# E180-Z8910SX.net
KiCad netlist of a schematic drawn in EAGLE
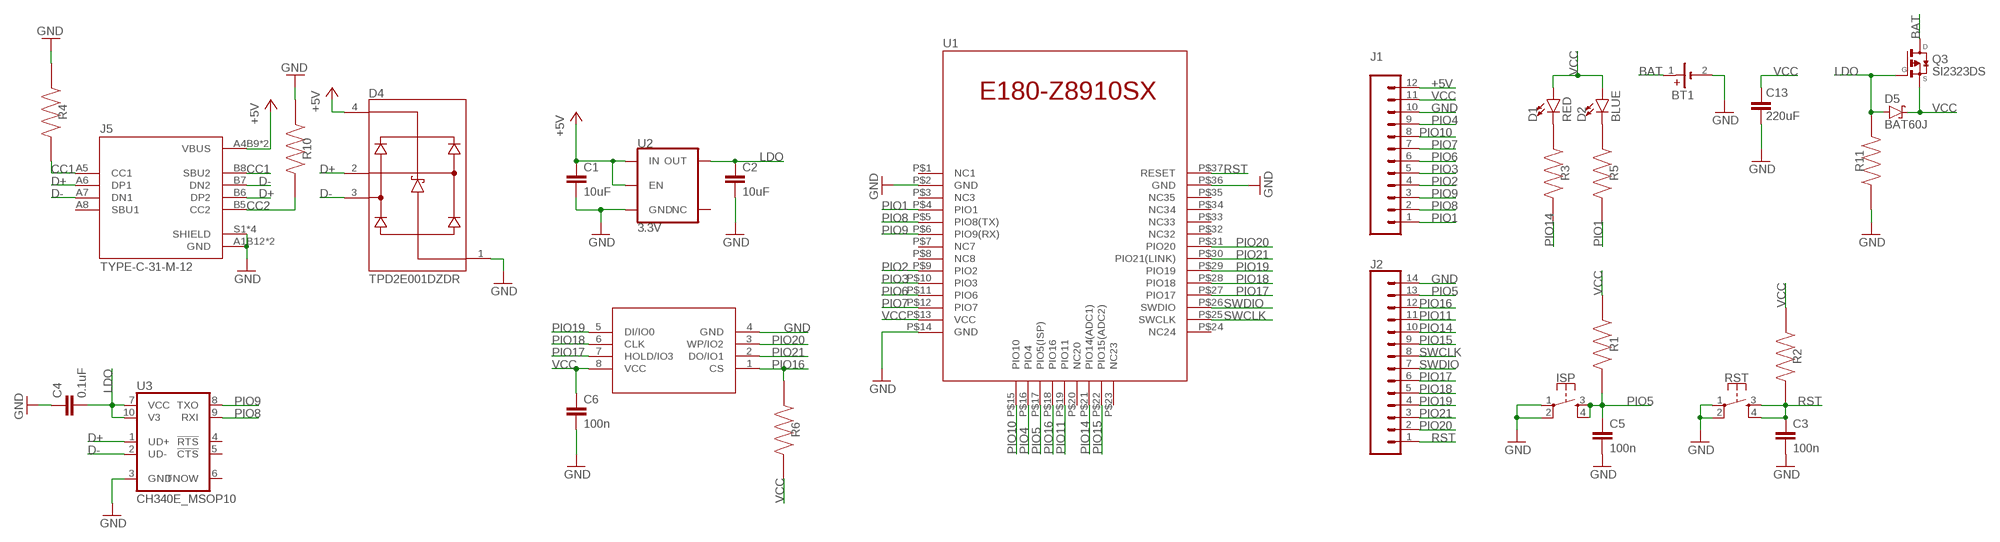
[diagram p0: schematic, sheet 1]

(export (version "E")
  (design (tool "Eeschema 10.0.6"))
  (components
    (comp (ref "BT1")
      (value "79527141")
      (footprint "eagle-import:79527141")
      (fields
        (field (name "DIGIKEY_PART_NO") "732-12325-2-ND")
        (field (name "MANUFACTURER") "Wurth Electronics Inc.")
        (field (name "CREATED_BY") "PCBLayout.com")
      )
      (libsource (lib "eagle-import") (part "79527141"))
    )
    (comp (ref "C1")
      (value "10uF")
      (footprint "eagle-import:0603")
      (libsource (lib "eagle-import") (part "10UF-0603-6.3V-20%"))
    )
    (comp (ref "C2")
      (value "10uF")
      (footprint "eagle-import:0603")
      (libsource (lib "eagle-import") (part "10UF-0603-6.3V-20%"))
    )
    (comp (ref "C3")
      (value "100n")
      (footprint "eagle-import:0603")
      (libsource (lib "eagle-import") (part "SparkFun-Capacitors_510_0.1UF-0603-25V-5%"))
    )
    (comp (ref "C4")
      (value "0.1uF")
      (footprint "eagle-import:0603")
      (libsource (lib "eagle-import") (part "0.1UF-0603-25V-(+80/-20%)"))
    )
    (comp (ref "C5")
      (value "100n")
      (footprint "eagle-import:0603")
      (libsource (lib "eagle-import") (part "SparkFun-Capacitors_510_0.1UF-0603-25V-5%"))
    )
    (comp (ref "C6")
      (value "100n")
      (footprint "eagle-import:0603")
      (libsource (lib "eagle-import") (part "SparkFun-Capacitors_510_0.1UF-0603-25V-5%"))
    )
    (comp (ref "C13")
      (value "220uF")
      (footprint "eagle-import:CAPM7343X310")
      (libsource (lib "eagle-import") (part "CTANTALUM-2917(7343-METRIC)_"))
    )
    (comp (ref "D1")
      (value "RED")
      (footprint "eagle-import:LED-0603")
      (libsource (lib "eagle-import") (part "LED-RED0603"))
    )
    (comp (ref "D2")
      (value "BLUE")
      (footprint "eagle-import:LED-0603")
      (libsource (lib "eagle-import") (part "LED-GREEN0603"))
    )
    (comp (ref "D4")
      (value "TPD2E001DZDR")
      (footprint "eagle-import:SOT192P237X122-4N")
      (fields (field (name "MF") "Texas Instruments"))
      (libsource (lib "eagle-import") (part "TPD2E001DZDR"))
    )
    (comp (ref "D5")
      (value "BAT60J")
      (footprint "eagle-import:SOD323_ST")
      (libsource (lib "eagle-import") (part "BAT60J"))
    )
    (comp (ref "ISP")
      (value "MOMENTARY-SWITCH-SPST-2-SMD-4.6X2.8MM")
      (footprint "eagle-import:TACTILE_SWITCH_SMD_4.6X2.8MM")
      (libsource (lib "eagle-import") (part "MOMENTARY-SWITCH-SPST-2-SMD-4.6X2.8MM"))
    )
    (comp (ref "J1")
      (value "CONN_12NO_SILK")
      (footprint "eagle-import:1X12_NO_SILK")
      (libsource (lib "eagle-import") (part "CONN_12NO_SILK"))
    )
    (comp (ref "J2")
      (value "CONN_14NO_SILK")
      (footprint "eagle-import:1X14_NO_SILK")
      (libsource (lib "eagle-import") (part "CONN_14NO_SILK"))
    )
    (comp (ref "J5")
      (value "TYPE-C-31-M-12")
      (footprint "eagle-import:HRO_TYPE-C-31-M-12")
      (fields (field (name "MF") "HRO Electronics Co., Ltd."))
      (libsource (lib "eagle-import") (part "TYPE-C-31-M-12"))
    )
    (comp (ref "Q3")
      (value "SI2323DS")
      (footprint "eagle-import:SOT23")
      (fields (field (name "MF") "Vishay Siliconix"))
      (libsource (lib "eagle-import") (part "SI2323DS"))
    )
    (comp (ref "R1")
      (value "10k")
      (footprint "eagle-import:RESC1005X40N")
      (fields (field (name "MF") "Yageo") (field (name "MP") "RC0402FR-073M6L"))
      (libsource (lib "eagle-import") (part "RC0402FR-073M6L"))
    )
    (comp (ref "R2")
      (value "10k")
      (footprint "eagle-import:RESC1005X40N")
      (fields (field (name "MF") "Yageo") (field (name "MP") "RC0402FR-073M6L"))
      (libsource (lib "eagle-import") (part "RC0402FR-073M6L"))
    )
    (comp (ref "R3")
      (value "2k")
      (footprint "eagle-import:RESC1005X40N")
      (fields (field (name "MF") "Yageo") (field (name "MP") "RC0402FR-073M6L"))
      (libsource (lib "eagle-import") (part "RC0402FR-073M6L"))
    )
    (comp (ref "R4")
      (value "5.1k")
      (footprint "eagle-import:RESC1005X40N")
      (fields (field (name "MF") "Yageo") (field (name "MP") "RC0402FR-073M6L"))
      (libsource (lib "eagle-import") (part "RC0402FR-073M6L"))
    )
    (comp (ref "R5")
      (value "2k")
      (footprint "eagle-import:RESC1005X40N")
      (fields (field (name "MF") "Yageo") (field (name "MP") "RC0402FR-073M6L"))
      (libsource (lib "eagle-import") (part "RC0402FR-073M6L"))
    )
    (comp (ref "R6")
      (value "100k")
      (footprint "eagle-import:RESC1005X40N")
      (fields (field (name "MF") "Yageo") (field (name "MP") "RC0402FR-073M6L"))
      (libsource (lib "eagle-import") (part "RC0402FR-073M6L"))
    )
    (comp (ref "R10")
      (value "5.1k")
      (footprint "eagle-import:RESC1005X40N")
      (fields (field (name "MF") "Yageo") (field (name "MP") "RC0402FR-073M6L"))
      (libsource (lib "eagle-import") (part "RC0402FR-073M6L"))
    )
    (comp (ref "R11")
      (value "10k")
      (footprint "eagle-import:RESC1005X40N")
      (fields (field (name "MF") "Yageo") (field (name "MP") "RC0402FR-073M6L"))
      (libsource (lib "eagle-import") (part "RC0402FR-073M6L"))
    )
    (comp (ref "RST")
      (value "MOMENTARY-SWITCH-SPST-2-SMD-4.6X2.8MM")
      (footprint "eagle-import:TACTILE_SWITCH_SMD_4.6X2.8MM")
      (libsource (lib "eagle-import") (part "MOMENTARY-SWITCH-SPST-2-SMD-4.6X2.8MM"))
    )
    (comp (ref "U$1")
      (value "W25Q80DVSNIG")
      (footprint "eagle-import:SO-8")
      (fields (field (name "MF") "Winbond Electronics") (field (name "MP") "W25Q80BVSNIG"))
      (libsource (lib "eagle-import") (part "W25Q80BVSNIG"))
    )
    (comp (ref "U1")
      (value "E180-Z8910SXE180-Z8910SP")
      (footprint "eagle-import:E180-Z8910SX")
      (libsource (lib "eagle-import") (part "E180-Z8910SXE180-Z8910SP"))
    )
    (comp (ref "U2")
      (value "3.3V")
      (footprint "eagle-import:SOT23-5")
      (libsource (lib "eagle-import") (part "V_REG_AP2112K-3.3V"))
    )
    (comp (ref "U3")
      (value "CH340E_MSOP10")
      (footprint "eagle-import:MSOP10")
      (fields (field (name "MF") "WCH") (field (name "MP") "CH340E"))
      (libsource (lib "eagle-import") (part "CH340E_MSOP10"))
    )
  )
  (nets
    (net (code "1") (name "+5V") (class "Default")
      (node (ref "C1") (pin "1") (pinfunction "1_1") (pintype "passive"))
      (node (ref "D4") (pin "4") (pinfunction "VCC_4") (pintype "power_in"))
      (node (ref "J1") (pin "12") (pinfunction "12_12") (pintype "passive"))
      (node (ref "J5") (pin "A4B9") (pinfunction "VBUS_A4B9") (pintype "power_in"))
      (node (ref "J5") (pin "B4A9") (pinfunction "VBUS_B4A9") (pintype "power_in"))
      (node (ref "U2") (pin "1") (pinfunction "IN_1") (pintype "input"))
      (node (ref "U2") (pin "3") (pinfunction "EN_3") (pintype "input"))
    )
    (net (code "2") (name "/BAT") (class "Default")
      (node (ref "BT1") (pin "1") (pinfunction "+_1") (pintype "passive"))
      (node (ref "Q3") (pin "3") (pinfunction "D_3") (pintype "passive"))
    )
    (net (code "3") (name "/CC1") (class "Default")
      (node (ref "J5") (pin "A5") (pinfunction "CC1_A5") (pintype "bidirectional"))
      (node (ref "J5") (pin "B8") (pinfunction "SBU2_B8") (pintype "bidirectional"))
      (node (ref "R4") (pin "2") (pinfunction "2_2") (pintype "passive"))
    )
    (net (code "4") (name "/CC2") (class "Default")
      (node (ref "J5") (pin "B5") (pinfunction "CC2_B5") (pintype "bidirectional"))
      (node (ref "R10") (pin "2") (pinfunction "2_2") (pintype "passive"))
    )
    (net (code "5") (name "/D+") (class "Default")
      (node (ref "D4") (pin "2") (pinfunction "IO1_2") (pintype "bidirectional"))
      (node (ref "J5") (pin "A6") (pinfunction "DP1_A6") (pintype "bidirectional"))
      (node (ref "J5") (pin "B6") (pinfunction "DP2_B6") (pintype "bidirectional"))
      (node (ref "U3") (pin "1") (pinfunction "UD+_1") (pintype "bidirectional"))
    )
    (net (code "6") (name "/D-") (class "Default")
      (node (ref "D4") (pin "3") (pinfunction "IO2_3") (pintype "bidirectional"))
      (node (ref "J5") (pin "A7") (pinfunction "DN1_A7") (pintype "bidirectional"))
      (node (ref "J5") (pin "B7") (pinfunction "DN2_B7") (pintype "bidirectional"))
      (node (ref "U3") (pin "2") (pinfunction "UD-_2") (pintype "bidirectional"))
    )
    (net (code "7") (name "/LDO") (class "Default")
      (node (ref "C2") (pin "1") (pinfunction "1_1") (pintype "passive"))
      (node (ref "C4") (pin "2") (pinfunction "2_2") (pintype "passive"))
      (node (ref "D5") (pin "A") (pinfunction "A_A") (pintype "passive"))
      (node (ref "Q3") (pin "1") (pinfunction "G_1") (pintype "passive"))
      (node (ref "R11") (pin "2") (pinfunction "2_2") (pintype "passive"))
      (node (ref "U2") (pin "5") (pinfunction "OUT_5") (pintype "passive"))
      (node (ref "U3") (pin "10") (pinfunction "V3_10") (pintype "bidirectional"))
      (node (ref "U3") (pin "7") (pinfunction "VCC_7") (pintype "bidirectional"))
    )
    (net (code "8") (name "/PIO1") (class "Default")
      (node (ref "J1") (pin "1") (pinfunction "1_1") (pintype "passive"))
      (node (ref "R5") (pin "2") (pinfunction "2_2") (pintype "passive"))
      (node (ref "U1") (pin "P$4") (pinfunction "PIO1_P$4") (pintype "bidirectional"))
    )
    (net (code "9") (name "/PIO2") (class "Default")
      (node (ref "J1") (pin "4") (pinfunction "4_4") (pintype "passive"))
      (node (ref "U1") (pin "P$9") (pinfunction "PIO2_P$9") (pintype "bidirectional"))
    )
    (net (code "10") (name "/PIO3") (class "Default")
      (node (ref "J1") (pin "5") (pinfunction "5_5") (pintype "passive"))
      (node (ref "U1") (pin "P$10") (pinfunction "PIO3_P$10") (pintype "bidirectional"))
    )
    (net (code "11") (name "/PIO4") (class "Default")
      (node (ref "J1") (pin "9") (pinfunction "9_9") (pintype "passive"))
      (node (ref "U1") (pin "P$16") (pinfunction "PIO4_P$16") (pintype "bidirectional"))
    )
    (net (code "12") (name "/PIO5") (class "Default")
      (node (ref "C5") (pin "1") (pinfunction "1_1") (pintype "passive"))
      (node (ref "ISP") (pin "3") (pinfunction "3_3") (pintype "passive"))
      (node (ref "ISP") (pin "4") (pinfunction "4_4") (pintype "passive"))
      (node (ref "J2") (pin "13") (pinfunction "13_13") (pintype "passive"))
      (node (ref "R1") (pin "2") (pinfunction "2_2") (pintype "passive"))
      (node (ref "U1") (pin "P$17") (pinfunction "PIO5(ISP)_P$17") (pintype "bidirectional"))
    )
    (net (code "13") (name "/PIO6") (class "Default")
      (node (ref "J1") (pin "6") (pinfunction "6_6") (pintype "passive"))
      (node (ref "U1") (pin "P$11") (pinfunction "PIO6_P$11") (pintype "bidirectional"))
    )
    (net (code "14") (name "/PIO7") (class "Default")
      (node (ref "J1") (pin "7") (pinfunction "7_7") (pintype "passive"))
      (node (ref "U1") (pin "P$12") (pinfunction "PIO7_P$12") (pintype "bidirectional"))
    )
    (net (code "15") (name "/PIO8") (class "Default")
      (node (ref "J1") (pin "2") (pinfunction "2_2") (pintype "passive"))
      (node (ref "U1") (pin "P$5") (pinfunction "PIO8(TX)_P$5") (pintype "bidirectional"))
      (node (ref "U3") (pin "9") (pinfunction "RXI_9") (pintype "bidirectional"))
    )
    (net (code "16") (name "/PIO9") (class "Default")
      (node (ref "J1") (pin "3") (pinfunction "3_3") (pintype "passive"))
      (node (ref "U1") (pin "P$6") (pinfunction "PIO9(RX)_P$6") (pintype "bidirectional"))
      (node (ref "U3") (pin "8") (pinfunction "TXO_8") (pintype "bidirectional"))
    )
    (net (code "17") (name "/PIO10") (class "Default")
      (node (ref "J1") (pin "8") (pinfunction "8_8") (pintype "passive"))
      (node (ref "U1") (pin "P$15") (pinfunction "PIO10_P$15") (pintype "bidirectional"))
    )
    (net (code "18") (name "/PIO11") (class "Default")
      (node (ref "J2") (pin "11") (pinfunction "11_11") (pintype "passive"))
      (node (ref "U1") (pin "P$19") (pinfunction "PIO11_P$19") (pintype "bidirectional"))
    )
    (net (code "19") (name "/PIO14") (class "Default")
      (node (ref "J2") (pin "10") (pinfunction "10_10") (pintype "passive"))
      (node (ref "R3") (pin "2") (pinfunction "2_2") (pintype "passive"))
      (node (ref "U1") (pin "P$21") (pinfunction "PIO14(ADC1)_P$21") (pintype "bidirectional"))
    )
    (net (code "20") (name "/PIO15") (class "Default")
      (node (ref "J2") (pin "9") (pinfunction "9_9") (pintype "passive"))
      (node (ref "U1") (pin "P$22") (pinfunction "PIO15(ADC2)_P$22") (pintype "bidirectional"))
    )
    (net (code "21") (name "/PIO16") (class "Default")
      (node (ref "J2") (pin "12") (pinfunction "12_12") (pintype "passive"))
      (node (ref "R6") (pin "1") (pinfunction "1_1") (pintype "passive"))
      (node (ref "U$1") (pin "1") (pinfunction "CS_1") (pintype "bidirectional"))
      (node (ref "U1") (pin "P$18") (pinfunction "PIO16_P$18") (pintype "bidirectional"))
    )
    (net (code "22") (name "/PIO17") (class "Default")
      (node (ref "J2") (pin "6") (pinfunction "6_6") (pintype "passive"))
      (node (ref "U$1") (pin "7") (pinfunction "HOLD/IO3_7") (pintype "bidirectional"))
      (node (ref "U1") (pin "P$27") (pinfunction "PIO17_P$27") (pintype "bidirectional"))
    )
    (net (code "23") (name "/PIO18") (class "Default")
      (node (ref "J2") (pin "5") (pinfunction "5_5") (pintype "passive"))
      (node (ref "U$1") (pin "6") (pinfunction "CLK_6") (pintype "bidirectional"))
      (node (ref "U1") (pin "P$28") (pinfunction "PIO18_P$28") (pintype "bidirectional"))
    )
    (net (code "24") (name "/PIO19") (class "Default")
      (node (ref "J2") (pin "4") (pinfunction "4_4") (pintype "passive"))
      (node (ref "U$1") (pin "5") (pinfunction "DI/IO0_5") (pintype "bidirectional"))
      (node (ref "U1") (pin "P$29") (pinfunction "PIO19_P$29") (pintype "bidirectional"))
    )
    (net (code "25") (name "/PIO20") (class "Default")
      (node (ref "J2") (pin "2") (pinfunction "2_2") (pintype "passive"))
      (node (ref "U$1") (pin "3") (pinfunction "WP/IO2_3") (pintype "bidirectional"))
      (node (ref "U1") (pin "P$31") (pinfunction "PIO20_P$31") (pintype "bidirectional"))
    )
    (net (code "26") (name "/PIO21") (class "Default")
      (node (ref "J2") (pin "3") (pinfunction "3_3") (pintype "passive"))
      (node (ref "U$1") (pin "2") (pinfunction "DO/IO1_2") (pintype "bidirectional"))
      (node (ref "U1") (pin "P$30") (pinfunction "PIO21(LINK)_P$30") (pintype "bidirectional"))
    )
    (net (code "27") (name "/RST") (class "Default")
      (node (ref "C3") (pin "1") (pinfunction "1_1") (pintype "passive"))
      (node (ref "J2") (pin "1") (pinfunction "1_1") (pintype "passive"))
      (node (ref "R2") (pin "2") (pinfunction "2_2") (pintype "passive"))
      (node (ref "RST") (pin "3") (pinfunction "3_3") (pintype "passive"))
      (node (ref "RST") (pin "4") (pinfunction "4_4") (pintype "passive"))
      (node (ref "U1") (pin "P$37") (pinfunction "RESET_P$37") (pintype "bidirectional"))
    )
    (net (code "28") (name "/SWCLK") (class "Default")
      (node (ref "J2") (pin "8") (pinfunction "8_8") (pintype "passive"))
      (node (ref "U1") (pin "P$25") (pinfunction "SWCLK_P$25") (pintype "bidirectional"))
    )
    (net (code "29") (name "/SWDIO") (class "Default")
      (node (ref "J2") (pin "7") (pinfunction "7_7") (pintype "passive"))
      (node (ref "U1") (pin "P$26") (pinfunction "SWDIO_P$26") (pintype "bidirectional"))
    )
    (net (code "30") (name "/VCC") (class "Default")
      (node (ref "C13") (pin "1") (pinfunction "1_1") (pintype "passive"))
      (node (ref "C6") (pin "1") (pinfunction "1_1") (pintype "passive"))
      (node (ref "D1") (pin "A") (pinfunction "A_A") (pintype "passive"))
      (node (ref "D2") (pin "A") (pinfunction "A_A") (pintype "passive"))
      (node (ref "D5") (pin "C") (pinfunction "C_C") (pintype "passive"))
      (node (ref "J1") (pin "11") (pinfunction "11_11") (pintype "passive"))
      (node (ref "Q3") (pin "2") (pinfunction "S_2") (pintype "passive"))
      (node (ref "R1") (pin "1") (pinfunction "1_1") (pintype "passive"))
      (node (ref "R2") (pin "1") (pinfunction "1_1") (pintype "passive"))
      (node (ref "R6") (pin "2") (pinfunction "2_2") (pintype "passive"))
      (node (ref "U$1") (pin "8") (pinfunction "VCC_8") (pintype "bidirectional"))
      (node (ref "U1") (pin "P$13") (pinfunction "VCC_P$13") (pintype "bidirectional"))
    )
    (net (code "31") (name "GND") (class "Default")
      (node (ref "BT1") (pin "2") (pinfunction "-_2") (pintype "passive"))
      (node (ref "C1") (pin "2") (pinfunction "2_2") (pintype "passive"))
      (node (ref "C13") (pin "2") (pinfunction "2_2") (pintype "passive"))
      (node (ref "C2") (pin "2") (pinfunction "2_2") (pintype "passive"))
      (node (ref "C3") (pin "2") (pinfunction "2_2") (pintype "passive"))
      (node (ref "C4") (pin "1") (pinfunction "1_1") (pintype "passive"))
      (node (ref "C5") (pin "2") (pinfunction "2_2") (pintype "passive"))
      (node (ref "C6") (pin "2") (pinfunction "2_2") (pintype "passive"))
      (node (ref "D4") (pin "1") (pinfunction "GND_1") (pintype "power_in"))
      (node (ref "ISP") (pin "1") (pinfunction "1_1") (pintype "passive"))
      (node (ref "ISP") (pin "2") (pinfunction "2_2") (pintype "passive"))
      (node (ref "J1") (pin "10") (pinfunction "10_10") (pintype "passive"))
      (node (ref "J2") (pin "14") (pinfunction "14_14") (pintype "passive"))
      (node (ref "J5") (pin "A1B12") (pinfunction "GND_A1B12") (pintype "power_in"))
      (node (ref "J5") (pin "B1A12") (pinfunction "GND_B1A12") (pintype "power_in"))
      (node (ref "J5") (pin "S1") (pinfunction "SHIELD_S1") (pintype "passive"))
      (node (ref "J5") (pin "S2") (pinfunction "SHIELD_S2") (pintype "passive"))
      (node (ref "J5") (pin "S3") (pinfunction "SHIELD_S3") (pintype "passive"))
      (node (ref "J5") (pin "S4") (pinfunction "SHIELD_S4") (pintype "passive"))
      (node (ref "R10") (pin "1") (pinfunction "1_1") (pintype "passive"))
      (node (ref "R11") (pin "1") (pinfunction "1_1") (pintype "passive"))
      (node (ref "R4") (pin "1") (pinfunction "1_1") (pintype "passive"))
      (node (ref "RST") (pin "1") (pinfunction "1_1") (pintype "passive"))
      (node (ref "RST") (pin "2") (pinfunction "2_2") (pintype "passive"))
      (node (ref "U$1") (pin "4") (pinfunction "GND_4") (pintype "bidirectional"))
      (node (ref "U1") (pin "P$14") (pinfunction "GND_P$14") (pintype "bidirectional"))
      (node (ref "U1") (pin "P$2") (pinfunction "GND_P$2") (pintype "bidirectional"))
      (node (ref "U1") (pin "P$36") (pinfunction "GND_P$36") (pintype "bidirectional"))
      (node (ref "U2") (pin "2") (pinfunction "GND_2") (pintype "input"))
      (node (ref "U3") (pin "3") (pinfunction "GND_3") (pintype "bidirectional"))
    )
    (net (code "32") (name "Net-(D1-PadC)") (class "Default")
      (node (ref "D1") (pin "C") (pinfunction "C_C") (pintype "passive"))
      (node (ref "R3") (pin "1") (pinfunction "1_1") (pintype "passive"))
    )
    (net (code "33") (name "Net-(D2-PadC)") (class "Default")
      (node (ref "D2") (pin "C") (pinfunction "C_C") (pintype "passive"))
      (node (ref "R5") (pin "1") (pinfunction "1_1") (pintype "passive"))
    )
    (net (code "34") (name "unconnected-(J5-SBU1-PadA8)") (class "Default")
      (node (ref "J5") (pin "A8") (pinfunction "SBU1_A8") (pintype "bidirectional"))
    )
    (net (code "35") (name "unconnected-(U1-NC1-PadP$1)") (class "Default")
      (node (ref "U1") (pin "P$1") (pinfunction "NC1_P$1") (pintype "bidirectional"))
    )
    (net (code "36") (name "unconnected-(U1-NC3-PadP$3)") (class "Default")
      (node (ref "U1") (pin "P$3") (pinfunction "NC3_P$3") (pintype "bidirectional"))
    )
    (net (code "37") (name "unconnected-(U1-NC7-PadP$7)") (class "Default")
      (node (ref "U1") (pin "P$7") (pinfunction "NC7_P$7") (pintype "bidirectional"))
    )
    (net (code "38") (name "unconnected-(U1-NC8-PadP$8)") (class "Default")
      (node (ref "U1") (pin "P$8") (pinfunction "NC8_P$8") (pintype "bidirectional"))
    )
    (net (code "39") (name "unconnected-(U1-NC20-PadP$20)") (class "Default")
      (node (ref "U1") (pin "P$20") (pinfunction "NC20_P$20") (pintype "bidirectional"))
    )
    (net (code "40") (name "unconnected-(U1-NC23-PadP$23)") (class "Default")
      (node (ref "U1") (pin "P$23") (pinfunction "NC23_P$23") (pintype "bidirectional"))
    )
    (net (code "41") (name "unconnected-(U1-NC24-PadP$24)") (class "Default")
      (node (ref "U1") (pin "P$24") (pinfunction "NC24_P$24") (pintype "bidirectional"))
    )
    (net (code "42") (name "unconnected-(U1-NC32-PadP$32)") (class "Default")
      (node (ref "U1") (pin "P$32") (pinfunction "NC32_P$32") (pintype "bidirectional"))
    )
    (net (code "43") (name "unconnected-(U1-NC33-PadP$33)") (class "Default")
      (node (ref "U1") (pin "P$33") (pinfunction "NC33_P$33") (pintype "bidirectional"))
    )
    (net (code "44") (name "unconnected-(U1-NC34-PadP$34)") (class "Default")
      (node (ref "U1") (pin "P$34") (pinfunction "NC34_P$34") (pintype "bidirectional"))
    )
    (net (code "45") (name "unconnected-(U1-NC35-PadP$35)") (class "Default")
      (node (ref "U1") (pin "P$35") (pinfunction "NC35_P$35") (pintype "bidirectional"))
    )
    (net (code "46") (name "unconnected-(U2-NC-Pad4)") (class "Default")
      (node (ref "U2") (pin "4") (pinfunction "NC_4") (pintype "no_connect"))
    )
    (net (code "47") (name "unconnected-(U3-TNOW-Pad6)") (class "Default")
      (node (ref "U3") (pin "6") (pinfunction "TNOW_6") (pintype "bidirectional"))
    )
    (net (code "48") (name "unconnected-(U3-~{CTS}-Pad5)") (class "Default")
      (node (ref "U3") (pin "5") (pinfunction "~{CTS}_5") (pintype "bidirectional"))
    )
    (net (code "49") (name "unconnected-(U3-~{RTS}-Pad4)") (class "Default")
      (node (ref "U3") (pin "4") (pinfunction "~{RTS}_4") (pintype "bidirectional"))
    )
  )
)
